# CarelessWISPer_alphaPCB.net
KiCad netlist of a schematic drawn in EAGLE
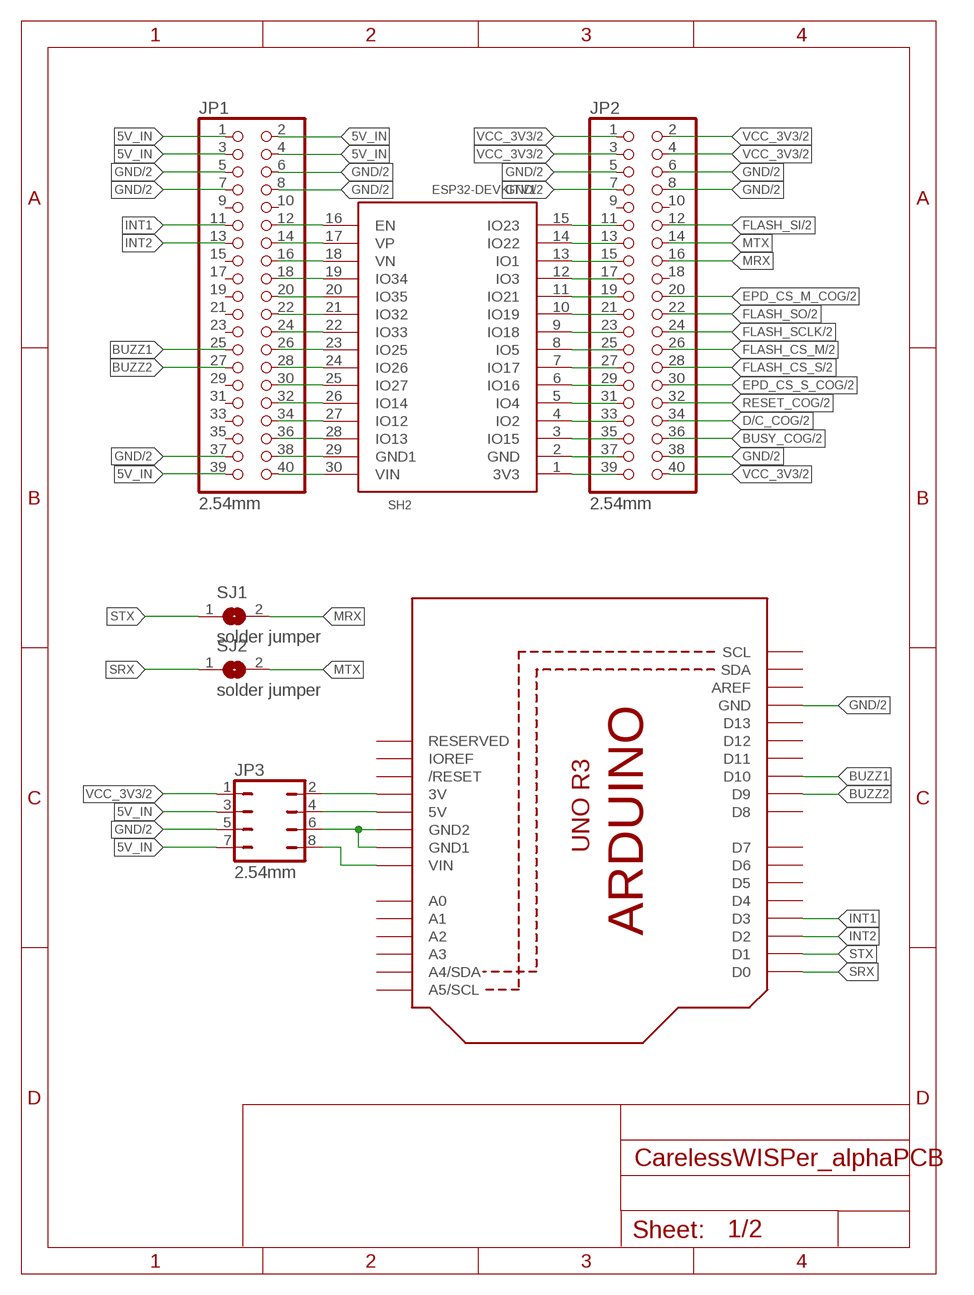
[diagram p0: schematic, sheet 1]
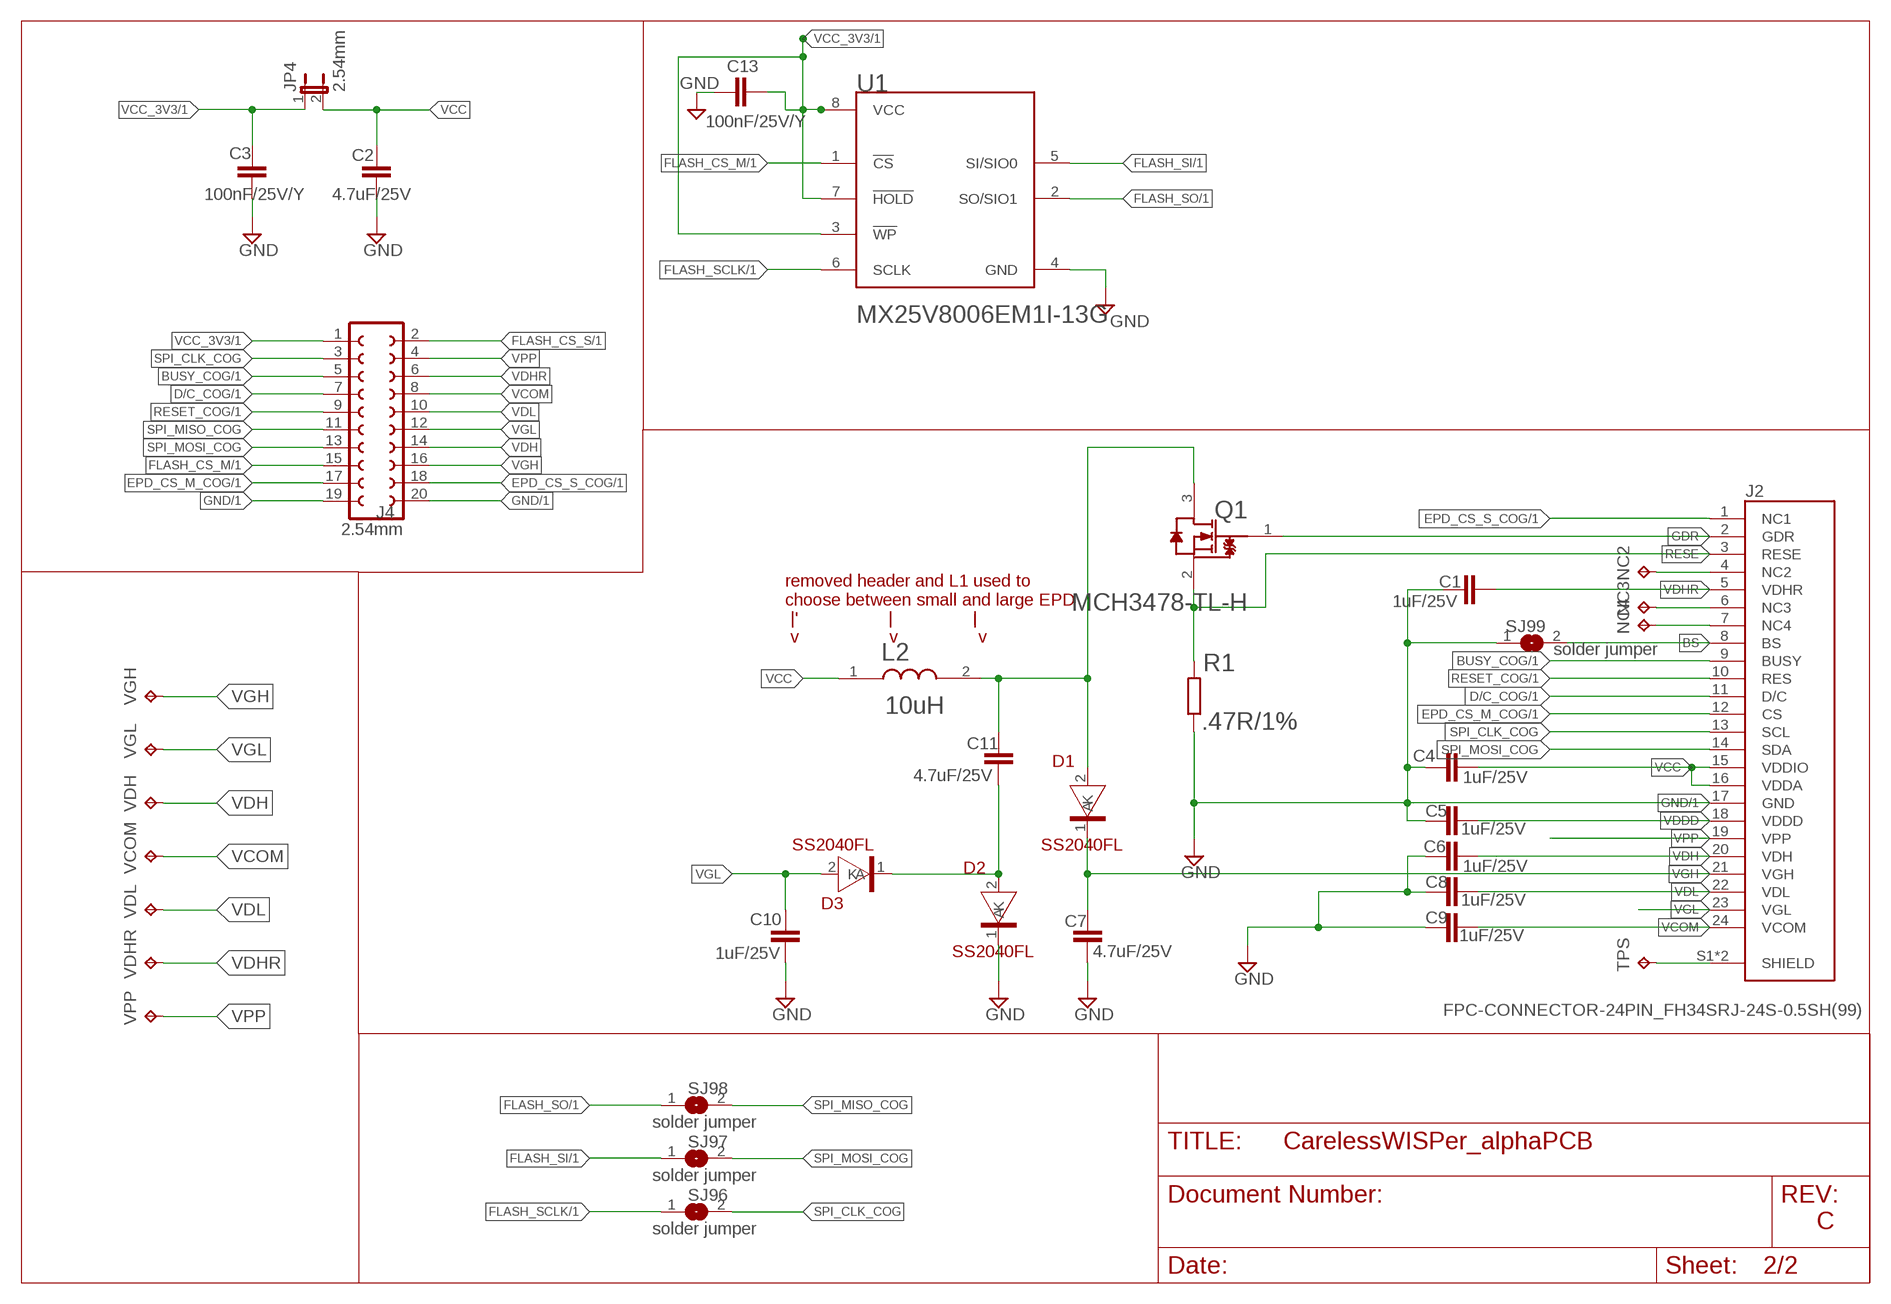
[diagram p1: schematic, sheet 2]

(export (version "E")
  (design (tool "Eeschema 10.0.6"))
  (components
    (comp (ref "JP1")
      (value "2.54mm")
      (footprint "eagle-import:2X20")
      (libsource (lib "eagle-import") (part "PINHD-2X20"))
    )
    (comp (ref "JP2")
      (value "2.54mm")
      (footprint "eagle-import:2X20")
      (libsource (lib "eagle-import") (part "PINHD-2X20"))
    )
    (comp (ref "JP3")
      (value "2.54mm")
      (footprint "eagle-import:JP4Q")
      (libsource (lib "eagle-import") (part "JP4Q"))
    )
    (comp (ref "SH1")
      (value "ARDUINOR3-BPLACE")
      (footprint "eagle-import:ARDUINOR3-BPLACE")
      (libsource (lib "eagle-import") (part "ARDUINOR3-BPLACE"))
    )
    (comp (ref "SH2")
      (value "ESP32-DEVKIT1_FIX")
      (footprint "eagle-import:ESP32-DEVKITV1")
      (libsource (lib "eagle-import") (part "ESP32-DEVKIT1_FIX"))
    )
    (comp (ref "SJ1")
      (value "solder jumper")
      (footprint "eagle-import:SJ")
      (libsource (lib "eagle-import") (part "SJ"))
    )
    (comp (ref "SJ2")
      (value "solder jumper")
      (footprint "eagle-import:SJ")
      (libsource (lib "eagle-import") (part "SJ"))
    )
    (comp (ref "C1")
      (value "1uF/25V")
      (footprint "eagle-import:CAPC2012X110")
      (libsource (lib "eagle-import") (part "CCHIP-0805(2012-METRIC)_"))
    )
    (comp (ref "C2")
      (value "4.7uF/25V")
      (footprint "eagle-import:CAPC2012X110")
      (libsource (lib "eagle-import") (part "CCHIP-0805(2012-METRIC)_"))
    )
    (comp (ref "C3")
      (value "100nF/25V/Y")
      (footprint "eagle-import:CAPC2012X110")
      (libsource (lib "eagle-import") (part "CCHIP-0805(2012-METRIC)_"))
    )
    (comp (ref "C4")
      (value "1uF/25V")
      (footprint "eagle-import:CAPC2012X110")
      (libsource (lib "eagle-import") (part "CCHIP-0805(2012-METRIC)_"))
    )
    (comp (ref "C5")
      (value "1uF/25V")
      (footprint "eagle-import:CAPC2012X110")
      (libsource (lib "eagle-import") (part "CCHIP-0805(2012-METRIC)_"))
    )
    (comp (ref "C6")
      (value "1uF/25V")
      (footprint "eagle-import:CAPC2012X110")
      (libsource (lib "eagle-import") (part "CCHIP-0805(2012-METRIC)_"))
    )
    (comp (ref "C7")
      (value "4.7uF/25V")
      (footprint "eagle-import:CAPC2012X110")
      (libsource (lib "eagle-import") (part "CCHIP-0805(2012-METRIC)_"))
    )
    (comp (ref "C8")
      (value "1uF/25V")
      (footprint "eagle-import:CAPC2012X110")
      (libsource (lib "eagle-import") (part "CCHIP-0805(2012-METRIC)_"))
    )
    (comp (ref "C9")
      (value "1uF/25V")
      (footprint "eagle-import:CAPC2012X110")
      (libsource (lib "eagle-import") (part "CCHIP-0805(2012-METRIC)_"))
    )
    (comp (ref "C10")
      (value "1uF/25V")
      (footprint "eagle-import:CAPC2012X110")
      (libsource (lib "eagle-import") (part "CCHIP-0805(2012-METRIC)_"))
    )
    (comp (ref "C11")
      (value "4.7uF/25V")
      (footprint "eagle-import:CAPC2012X110")
      (libsource (lib "eagle-import") (part "CCHIP-0805(2012-METRIC)_"))
    )
    (comp (ref "C13")
      (value "100nF/25V/Y")
      (footprint "eagle-import:CAPC2012X110")
      (libsource (lib "eagle-import") (part "CCHIP-0805(2012-METRIC)_"))
    )
    (comp (ref "D1")
      (value "SS2040FL")
      (footprint "eagle-import:SOD-123FL")
      (fields (field (name "MF") "Panjit"))
      (libsource (lib "eagle-import") (part "SS2040FL"))
    )
    (comp (ref "D2")
      (value "SS2040FL")
      (footprint "eagle-import:SOD-123FL")
      (fields (field (name "MF") "Panjit"))
      (libsource (lib "eagle-import") (part "SS2040FL"))
    )
    (comp (ref "D3")
      (value "SS2040FL")
      (footprint "eagle-import:SOD-123FL")
      (fields (field (name "MF") "Panjit"))
      (libsource (lib "eagle-import") (part "SS2040FL"))
    )
    (comp (ref "J2")
      (value "FPC-CONNECTOR-24PIN_FH34SRJ-24S-0.5SH(99)")
      (footprint "eagle-import:FPC-CONNECTOR-24PIN_HRS_FH34SRJ-24S-0.5SH(99)")
      (fields (field (name "MF") "Hirose Electric") (field (name "MP") "FH34SRJ-24S-0.5SH(99)"))
      (libsource (lib "eagle-import") (part "FPC-CONNECTOR-24PIN_FH34SRJ-24S-0.5SH(99)"))
    )
    (comp (ref "J4")
      (value "2.54mm")
      (footprint "eagle-import:FE10-2W")
      (libsource (lib "eagle-import") (part "FE10-2W"))
    )
    (comp (ref "JP4")
      (value "2.54mm")
      (footprint "eagle-import:JP1")
      (libsource (lib "eagle-import") (part "JP1E"))
    )
    (comp (ref "L2")
      (value "MURATA_LQH3NPZ100MMELMURATA_LQH3NPZ100MMEL_0_0")
      (footprint "eagle-import:MURATA_LQH3NPZ100MMEL_0")
      (fields
        (field (name "MF") "Murata")
        (field (name "MPN") "LQH3NPZ100MMEL")
        (field (name "TOLERANCE") "0.2")
      )
      (libsource (lib "eagle-import") (part "MURATA_LQH3NPZ100MMELMURATA_LQH3NPZ100MMEL_0_0"))
    )
    (comp (ref "NC2")
      (value "TPB1,27")
      (footprint "eagle-import:B1,27")
      (libsource (lib "eagle-import") (part "TPB1,27"))
    )
    (comp (ref "NC3")
      (value "TPB1,27")
      (footprint "eagle-import:B1,27")
      (libsource (lib "eagle-import") (part "TPB1,27"))
    )
    (comp (ref "NC4")
      (value "TPB1,27")
      (footprint "eagle-import:B1,27")
      (libsource (lib "eagle-import") (part "TPB1,27"))
    )
    (comp (ref "Q1")
      (value "ON_SEMICONDUCTOR_MCH3478-TL-HON_SEMICONDUCTOR_MCH3478-TL-H_0_0")
      (footprint "eagle-import:ON_SEMICONDUCTOR_MCH3478-TL-H_0")
      (fields (field (name "MF") "On Semiconductor") (field (name "MPN") "MCH3478-TL-H"))
      (libsource (lib "eagle-import") (part "ON_SEMICONDUCTOR_MCH3478-TL-HON_SEMICONDUCTOR_MCH3478-TL-H_0_0"))
    )
    (comp (ref "R1")
      (value ".47R/1%")
      (footprint "eagle-import:RESC2012X65")
      (libsource (lib "eagle-import") (part "RCHIP-0805(2012-METRIC)_"))
    )
    (comp (ref "SJ96")
      (value "solder jumper")
      (footprint "eagle-import:SJ")
      (libsource (lib "eagle-import") (part "SJ"))
    )
    (comp (ref "SJ97")
      (value "solder jumper")
      (footprint "eagle-import:SJ")
      (libsource (lib "eagle-import") (part "SJ"))
    )
    (comp (ref "SJ98")
      (value "solder jumper")
      (footprint "eagle-import:SJ")
      (libsource (lib "eagle-import") (part "SJ"))
    )
    (comp (ref "SJ99")
      (value "solder jumper")
      (footprint "eagle-import:SJ")
      (libsource (lib "eagle-import") (part "SJ"))
    )
    (comp (ref "TPS")
      (value "TPB1,27")
      (footprint "eagle-import:B1,27")
      (libsource (lib "eagle-import") (part "TPB1,27"))
    )
    (comp (ref "U1")
      (value "MACRONIX_MX25V8006EM1I-13GMACRONIX_MX25V8006EM1I-13G_0_0")
      (footprint "eagle-import:MACRONIX_MX25V8006EM1I-13G_0")
      (fields
        (field (name "3DS_PART_NUMBER") "521-00003")
        (field (name "DIGIKEY_PART_NUMBER") "1092-1118-ND")
        (field (name "MF") "Macronix")
      )
      (libsource (lib "eagle-import") (part "MACRONIX_MX25V8006EM1I-13GMACRONIX_MX25V8006EM1I-13G_0_0"))
    )
    (comp (ref "VCOM")
      (value "TPB1,27")
      (footprint "eagle-import:B1,27")
      (libsource (lib "eagle-import") (part "TPB1,27"))
    )
    (comp (ref "VDH")
      (value "TPB1,27")
      (footprint "eagle-import:B1,27")
      (libsource (lib "eagle-import") (part "TPB1,27"))
    )
    (comp (ref "VDHR")
      (value "TPB1,27")
      (footprint "eagle-import:B1,27")
      (libsource (lib "eagle-import") (part "TPB1,27"))
    )
    (comp (ref "VDL")
      (value "TPB1,27")
      (footprint "eagle-import:B1,27")
      (libsource (lib "eagle-import") (part "TPB1,27"))
    )
    (comp (ref "VGH")
      (value "TPB1,27")
      (footprint "eagle-import:B1,27")
      (libsource (lib "eagle-import") (part "TPB1,27"))
    )
    (comp (ref "VGL")
      (value "TPB1,27")
      (footprint "eagle-import:B1,27")
      (libsource (lib "eagle-import") (part "TPB1,27"))
    )
    (comp (ref "VPP")
      (value "TPB1,27")
      (footprint "eagle-import:B1,27")
      (libsource (lib "eagle-import") (part "TPB1,27"))
    )
  )
  (nets
    (net (code "1") (name "5V_IN") (class "Default")
      (node (ref "JP1") (pin "1") (pinfunction "1_1") (pintype "passive"))
      (node (ref "JP1") (pin "2") (pinfunction "2_2") (pintype "passive"))
      (node (ref "JP1") (pin "3") (pinfunction "3_3") (pintype "passive"))
      (node (ref "JP1") (pin "39") (pinfunction "39_39") (pintype "passive"))
      (node (ref "JP1") (pin "4") (pinfunction "4_4") (pintype "passive"))
      (node (ref "JP3") (pin "3") (pinfunction "3_3") (pintype "passive"))
      (node (ref "JP3") (pin "7") (pinfunction "7_7") (pintype "passive"))
    )
    (net (code "2") (name "BS") (class "Default")
      (node (ref "J2") (pin "8") (pinfunction "BS_8") (pintype "passive"))
      (node (ref "SJ99") (pin "2") (pinfunction "2_2") (pintype "passive"))
    )
    (net (code "3") (name "BUSY_COG") (class "Default")
      (node (ref "J2") (pin "9") (pinfunction "BUSY_9") (pintype "passive"))
      (node (ref "J4") (pin "5") (pinfunction "5_5") (pintype "passive"))
      (node (ref "JP2") (pin "36") (pinfunction "36_36") (pintype "passive"))
    )
    (net (code "4") (name "BUZZ1") (class "Default")
      (node (ref "JP1") (pin "25") (pinfunction "25_25") (pintype "passive"))
      (node (ref "SH1") (pin "D10") (pinfunction "D10_D10") (pintype "bidirectional"))
    )
    (net (code "5") (name "BUZZ2") (class "Default")
      (node (ref "JP1") (pin "27") (pinfunction "27_27") (pintype "passive"))
      (node (ref "SH1") (pin "D9") (pinfunction "D9_D9") (pintype "bidirectional"))
    )
    (net (code "6") (name "D{slash}C_COG") (class "Default")
      (node (ref "J2") (pin "11") (pinfunction "D/C_11") (pintype "passive"))
      (node (ref "J4") (pin "7") (pinfunction "7_7") (pintype "passive"))
      (node (ref "JP2") (pin "34") (pinfunction "34_34") (pintype "passive"))
    )
    (net (code "7") (name "EPD_CS_M_COG") (class "Default")
      (node (ref "J2") (pin "12") (pinfunction "CS_12") (pintype "passive"))
      (node (ref "J4") (pin "17") (pinfunction "17_17") (pintype "passive"))
      (node (ref "JP2") (pin "20") (pinfunction "20_20") (pintype "passive"))
    )
    (net (code "8") (name "EPD_CS_S_COG") (class "Default")
      (node (ref "J2") (pin "1") (pinfunction "NC1_1") (pintype "passive"))
      (node (ref "J4") (pin "18") (pinfunction "18_18") (pintype "passive"))
      (node (ref "JP2") (pin "30") (pinfunction "30_30") (pintype "passive"))
    )
    (net (code "9") (name "FLASH_CS_M") (class "Default")
      (node (ref "J4") (pin "15") (pinfunction "15_15") (pintype "passive"))
      (node (ref "JP2") (pin "26") (pinfunction "26_26") (pintype "passive"))
      (node (ref "U1") (pin "1") (pinfunction "~{CS}_1") (pintype "input"))
    )
    (net (code "10") (name "FLASH_CS_S") (class "Default")
      (node (ref "J4") (pin "2") (pinfunction "2_2") (pintype "passive"))
      (node (ref "JP2") (pin "28") (pinfunction "28_28") (pintype "passive"))
    )
    (net (code "11") (name "FLASH_SCLK") (class "Default")
      (node (ref "JP2") (pin "24") (pinfunction "24_24") (pintype "passive"))
      (node (ref "SJ96") (pin "1") (pinfunction "1_1") (pintype "passive"))
      (node (ref "U1") (pin "6") (pinfunction "SCLK_6") (pintype "input"))
    )
    (net (code "12") (name "FLASH_SI") (class "Default")
      (node (ref "JP2") (pin "12") (pinfunction "12_12") (pintype "passive"))
      (node (ref "SJ97") (pin "1") (pinfunction "1_1") (pintype "passive"))
      (node (ref "U1") (pin "5") (pinfunction "SI/SIO0_5") (pintype "bidirectional"))
    )
    (net (code "13") (name "FLASH_SO") (class "Default")
      (node (ref "JP2") (pin "22") (pinfunction "22_22") (pintype "passive"))
      (node (ref "SJ98") (pin "1") (pinfunction "1_1") (pintype "passive"))
      (node (ref "U1") (pin "2") (pinfunction "SO/SIO1_2") (pintype "bidirectional"))
    )
    (net (code "14") (name "GDR") (class "Default")
      (node (ref "J2") (pin "2") (pinfunction "GDR_2") (pintype "passive"))
      (node (ref "Q1") (pin "1") (pinfunction "G_1") (pintype "passive"))
    )
    (net (code "15") (name "GND") (class "Default")
      (node (ref "C1") (pin "1") (pinfunction "1_1") (pintype "passive"))
      (node (ref "C10") (pin "2") (pinfunction "2_2") (pintype "passive"))
      (node (ref "C13") (pin "1") (pinfunction "1_1") (pintype "passive"))
      (node (ref "C2") (pin "1") (pinfunction "1_1") (pintype "passive"))
      (node (ref "C3") (pin "1") (pinfunction "1_1") (pintype "passive"))
      (node (ref "C4") (pin "2") (pinfunction "2_2") (pintype "passive"))
      (node (ref "C5") (pin "2") (pinfunction "2_2") (pintype "passive"))
      (node (ref "C6") (pin "2") (pinfunction "2_2") (pintype "passive"))
      (node (ref "C7") (pin "1") (pinfunction "1_1") (pintype "passive"))
      (node (ref "C8") (pin "2") (pinfunction "2_2") (pintype "passive"))
      (node (ref "C9") (pin "2") (pinfunction "2_2") (pintype "passive"))
      (node (ref "D2") (pin "1") (pinfunction "K_1") (pintype "passive"))
      (node (ref "J2") (pin "17") (pinfunction "GND_17") (pintype "passive"))
      (node (ref "J4") (pin "19") (pinfunction "19_19") (pintype "passive"))
      (node (ref "J4") (pin "20") (pinfunction "20_20") (pintype "passive"))
      (node (ref "JP1") (pin "37") (pinfunction "37_37") (pintype "passive"))
      (node (ref "JP1") (pin "5") (pinfunction "5_5") (pintype "passive"))
      (node (ref "JP1") (pin "6") (pinfunction "6_6") (pintype "passive"))
      (node (ref "JP1") (pin "7") (pinfunction "7_7") (pintype "passive"))
      (node (ref "JP1") (pin "8") (pinfunction "8_8") (pintype "passive"))
      (node (ref "JP2") (pin "38") (pinfunction "38_38") (pintype "passive"))
      (node (ref "JP2") (pin "5") (pinfunction "5_5") (pintype "passive"))
      (node (ref "JP2") (pin "6") (pinfunction "6_6") (pintype "passive"))
      (node (ref "JP2") (pin "7") (pinfunction "7_7") (pintype "passive"))
      (node (ref "JP2") (pin "8") (pinfunction "8_8") (pintype "passive"))
      (node (ref "JP3") (pin "5") (pinfunction "5_5") (pintype "passive"))
      (node (ref "R1") (pin "1") (pinfunction "1_1") (pintype "passive"))
      (node (ref "SH1") (pin "GND") (pinfunction "GND_GND") (pintype "power_in"))
      (node (ref "SJ99") (pin "1") (pinfunction "1_1") (pintype "passive"))
      (node (ref "U1") (pin "4") (pinfunction "GND_4") (pintype "power_in"))
    )
    (net (code "16") (name "INT1") (class "Default")
      (node (ref "JP1") (pin "11") (pinfunction "11_11") (pintype "passive"))
      (node (ref "SH1") (pin "D3") (pinfunction "D3_D3") (pintype "bidirectional"))
    )
    (net (code "17") (name "INT2") (class "Default")
      (node (ref "JP1") (pin "13") (pinfunction "13_13") (pintype "passive"))
      (node (ref "SH1") (pin "D2") (pinfunction "D2_D2") (pintype "bidirectional"))
    )
    (net (code "18") (name "MRX") (class "Default")
      (node (ref "JP2") (pin "16") (pinfunction "16_16") (pintype "passive"))
      (node (ref "SJ1") (pin "2") (pinfunction "2_2") (pintype "passive"))
    )
    (net (code "19") (name "MTX") (class "Default")
      (node (ref "JP2") (pin "14") (pinfunction "14_14") (pintype "passive"))
      (node (ref "SJ2") (pin "2") (pinfunction "2_2") (pintype "passive"))
    )
    (net (code "20") (name "Net-(D1-A)") (class "Default")
      (node (ref "C11") (pin "2") (pinfunction "2_2") (pintype "passive"))
      (node (ref "D1") (pin "2") (pinfunction "A_2") (pintype "passive"))
      (node (ref "L2") (pin "2") (pinfunction "2_2") (pintype "passive"))
      (node (ref "Q1") (pin "3") (pinfunction "D_3") (pintype "passive"))
    )
    (net (code "21") (name "Net-(D2-A)") (class "Default")
      (node (ref "C11") (pin "1") (pinfunction "1_1") (pintype "passive"))
      (node (ref "D2") (pin "2") (pinfunction "A_2") (pintype "passive"))
      (node (ref "D3") (pin "1") (pinfunction "K_1") (pintype "passive"))
    )
    (net (code "22") (name "Net-(J2-NC2)") (class "Default")
      (node (ref "J2") (pin "4") (pinfunction "NC2_4") (pintype "passive"))
      (node (ref "NC2") (pin "TP") (pinfunction "TP_TP") (pintype "input"))
    )
    (net (code "23") (name "Net-(J2-NC3)") (class "Default")
      (node (ref "J2") (pin "6") (pinfunction "NC3_6") (pintype "passive"))
      (node (ref "NC3") (pin "TP") (pinfunction "TP_TP") (pintype "input"))
    )
    (net (code "24") (name "Net-(J2-NC4)") (class "Default")
      (node (ref "J2") (pin "7") (pinfunction "NC4_7") (pintype "passive"))
      (node (ref "NC4") (pin "TP") (pinfunction "TP_TP") (pintype "input"))
    )
    (net (code "25") (name "Net-(J2-SHIELD-PadS1)") (class "Default")
      (node (ref "J2") (pin "S1") (pinfunction "SHIELD_S1") (pintype "passive"))
      (node (ref "J2") (pin "S2") (pinfunction "SHIELD_S2") (pintype "passive"))
      (node (ref "TPS") (pin "TP") (pinfunction "TP_TP") (pintype "input"))
    )
    (net (code "26") (name "Net-(JP3-Pad2)") (class "Default")
      (node (ref "JP3") (pin "2") (pinfunction "2_2") (pintype "passive"))
      (node (ref "SH1") (pin "3V") (pinfunction "3V_3V") (pintype "power_in"))
    )
    (net (code "27") (name "Net-(JP3-Pad4)") (class "Default")
      (node (ref "JP3") (pin "4") (pinfunction "4_4") (pintype "passive"))
      (node (ref "SH1") (pin "5V") (pinfunction "5V_5V") (pintype "power_in"))
    )
    (net (code "28") (name "Net-(JP3-Pad6)") (class "Default")
      (node (ref "JP3") (pin "6") (pinfunction "6_6") (pintype "passive"))
      (node (ref "SH1") (pin "GND1") (pinfunction "GND1_GND1") (pintype "power_in"))
      (node (ref "SH1") (pin "GND2") (pinfunction "GND2_GND2") (pintype "power_in"))
    )
    (net (code "29") (name "Net-(JP3-Pad8)") (class "Default")
      (node (ref "JP3") (pin "8") (pinfunction "8_8") (pintype "passive"))
      (node (ref "SH1") (pin "VIN") (pinfunction "VIN_VIN") (pintype "power_in"))
    )
    (net (code "30") (name "Net-(SH2-3V3)") (class "Default")
      (node (ref "JP2") (pin "39") (pinfunction "39_39") (pintype "passive"))
      (node (ref "SH2") (pin "1") (pinfunction "3V3_1") (pintype "bidirectional"))
    )
    (net (code "31") (name "Net-(SH2-EN)") (class "Default")
      (node (ref "JP1") (pin "12") (pinfunction "12_12") (pintype "passive"))
      (node (ref "SH2") (pin "16") (pinfunction "EN_16") (pintype "bidirectional"))
    )
    (net (code "32") (name "Net-(SH2-GND)") (class "Default")
      (node (ref "JP2") (pin "37") (pinfunction "37_37") (pintype "passive"))
      (node (ref "SH2") (pin "2") (pinfunction "GND_2") (pintype "bidirectional"))
    )
    (net (code "33") (name "Net-(SH2-GND1)") (class "Default")
      (node (ref "JP1") (pin "38") (pinfunction "38_38") (pintype "passive"))
      (node (ref "SH2") (pin "29") (pinfunction "GND1_29") (pintype "bidirectional"))
    )
    (net (code "34") (name "Net-(SH2-IO1)") (class "Default")
      (node (ref "JP2") (pin "15") (pinfunction "15_15") (pintype "passive"))
      (node (ref "SH2") (pin "13") (pinfunction "IO1_13") (pintype "bidirectional"))
    )
    (net (code "35") (name "Net-(SH2-IO2)") (class "Default")
      (node (ref "JP2") (pin "33") (pinfunction "33_33") (pintype "passive"))
      (node (ref "SH2") (pin "4") (pinfunction "IO2_4") (pintype "bidirectional"))
    )
    (net (code "36") (name "Net-(SH2-IO3)") (class "Default")
      (node (ref "JP2") (pin "17") (pinfunction "17_17") (pintype "passive"))
      (node (ref "SH2") (pin "12") (pinfunction "IO3_12") (pintype "bidirectional"))
    )
    (net (code "37") (name "Net-(SH2-IO4)") (class "Default")
      (node (ref "JP2") (pin "31") (pinfunction "31_31") (pintype "passive"))
      (node (ref "SH2") (pin "5") (pinfunction "IO4_5") (pintype "bidirectional"))
    )
    (net (code "38") (name "Net-(SH2-IO5)") (class "Default")
      (node (ref "JP2") (pin "25") (pinfunction "25_25") (pintype "passive"))
      (node (ref "SH2") (pin "8") (pinfunction "IO5_8") (pintype "bidirectional"))
    )
    (net (code "39") (name "Net-(SH2-IO12)") (class "Default")
      (node (ref "JP1") (pin "34") (pinfunction "34_34") (pintype "passive"))
      (node (ref "SH2") (pin "27") (pinfunction "IO12_27") (pintype "bidirectional"))
    )
    (net (code "40") (name "Net-(SH2-IO13)") (class "Default")
      (node (ref "JP1") (pin "36") (pinfunction "36_36") (pintype "passive"))
      (node (ref "SH2") (pin "28") (pinfunction "IO13_28") (pintype "bidirectional"))
    )
    (net (code "41") (name "Net-(SH2-IO14)") (class "Default")
      (node (ref "JP1") (pin "32") (pinfunction "32_32") (pintype "passive"))
      (node (ref "SH2") (pin "26") (pinfunction "IO14_26") (pintype "bidirectional"))
    )
    (net (code "42") (name "Net-(SH2-IO15)") (class "Default")
      (node (ref "JP2") (pin "35") (pinfunction "35_35") (pintype "passive"))
      (node (ref "SH2") (pin "3") (pinfunction "IO15_3") (pintype "bidirectional"))
    )
    (net (code "43") (name "Net-(SH2-IO16)") (class "Default")
      (node (ref "JP2") (pin "29") (pinfunction "29_29") (pintype "passive"))
      (node (ref "SH2") (pin "6") (pinfunction "IO16_6") (pintype "bidirectional"))
    )
    (net (code "44") (name "Net-(SH2-IO17)") (class "Default")
      (node (ref "JP2") (pin "27") (pinfunction "27_27") (pintype "passive"))
      (node (ref "SH2") (pin "7") (pinfunction "IO17_7") (pintype "bidirectional"))
    )
    (net (code "45") (name "Net-(SH2-IO18)") (class "Default")
      (node (ref "JP2") (pin "23") (pinfunction "23_23") (pintype "passive"))
      (node (ref "SH2") (pin "9") (pinfunction "IO18_9") (pintype "bidirectional"))
    )
    (net (code "46") (name "Net-(SH2-IO19)") (class "Default")
      (node (ref "JP2") (pin "21") (pinfunction "21_21") (pintype "passive"))
      (node (ref "SH2") (pin "10") (pinfunction "IO19_10") (pintype "bidirectional"))
    )
    (net (code "47") (name "Net-(SH2-IO21)") (class "Default")
      (node (ref "JP2") (pin "19") (pinfunction "19_19") (pintype "passive"))
      (node (ref "SH2") (pin "11") (pinfunction "IO21_11") (pintype "bidirectional"))
    )
    (net (code "48") (name "Net-(SH2-IO22)") (class "Default")
      (node (ref "JP2") (pin "13") (pinfunction "13_13") (pintype "passive"))
      (node (ref "SH2") (pin "14") (pinfunction "IO22_14") (pintype "bidirectional"))
    )
    (net (code "49") (name "Net-(SH2-IO23)") (class "Default")
      (node (ref "JP2") (pin "11") (pinfunction "11_11") (pintype "passive"))
      (node (ref "SH2") (pin "15") (pinfunction "IO23_15") (pintype "bidirectional"))
    )
    (net (code "50") (name "Net-(SH2-IO25)") (class "Default")
      (node (ref "JP1") (pin "26") (pinfunction "26_26") (pintype "passive"))
      (node (ref "SH2") (pin "23") (pinfunction "IO25_23") (pintype "bidirectional"))
    )
    (net (code "51") (name "Net-(SH2-IO26)") (class "Default")
      (node (ref "JP1") (pin "28") (pinfunction "28_28") (pintype "passive"))
      (node (ref "SH2") (pin "24") (pinfunction "IO26_24") (pintype "bidirectional"))
    )
    (net (code "52") (name "Net-(SH2-IO27)") (class "Default")
      (node (ref "JP1") (pin "30") (pinfunction "30_30") (pintype "passive"))
      (node (ref "SH2") (pin "25") (pinfunction "IO27_25") (pintype "bidirectional"))
    )
    (net (code "53") (name "Net-(SH2-IO32)") (class "Default")
      (node (ref "JP1") (pin "22") (pinfunction "22_22") (pintype "passive"))
      (node (ref "SH2") (pin "21") (pinfunction "IO32_21") (pintype "bidirectional"))
    )
    (net (code "54") (name "Net-(SH2-IO33)") (class "Default")
      (node (ref "JP1") (pin "24") (pinfunction "24_24") (pintype "passive"))
      (node (ref "SH2") (pin "22") (pinfunction "IO33_22") (pintype "bidirectional"))
    )
    (net (code "55") (name "Net-(SH2-IO34)") (class "Default")
      (node (ref "JP1") (pin "18") (pinfunction "18_18") (pintype "passive"))
      (node (ref "SH2") (pin "19") (pinfunction "IO34_19") (pintype "bidirectional"))
    )
    (net (code "56") (name "Net-(SH2-IO35)") (class "Default")
      (node (ref "JP1") (pin "20") (pinfunction "20_20") (pintype "passive"))
      (node (ref "SH2") (pin "20") (pinfunction "IO35_20") (pintype "bidirectional"))
    )
    (net (code "57") (name "Net-(SH2-VIN)") (class "Default")
      (node (ref "JP1") (pin "40") (pinfunction "40_40") (pintype "passive"))
      (node (ref "SH2") (pin "30") (pinfunction "VIN_30") (pintype "bidirectional"))
    )
    (net (code "58") (name "Net-(SH2-VN)") (class "Default")
      (node (ref "JP1") (pin "16") (pinfunction "16_16") (pintype "passive"))
      (node (ref "SH2") (pin "18") (pinfunction "VN_18") (pintype "bidirectional"))
    )
    (net (code "59") (name "Net-(SH2-VP)") (class "Default")
      (node (ref "JP1") (pin "14") (pinfunction "14_14") (pintype "passive"))
      (node (ref "SH2") (pin "17") (pinfunction "VP_17") (pintype "bidirectional"))
    )
    (net (code "60") (name "RESE") (class "Default")
      (node (ref "J2") (pin "3") (pinfunction "RESE_3") (pintype "passive"))
      (node (ref "Q1") (pin "2") (pinfunction "S_2") (pintype "passive"))
      (node (ref "R1") (pin "2") (pinfunction "2_2") (pintype "passive"))
    )
    (net (code "61") (name "RESET_COG") (class "Default")
      (node (ref "J2") (pin "10") (pinfunction "RES_10") (pintype "passive"))
      (node (ref "J4") (pin "9") (pinfunction "9_9") (pintype "passive"))
      (node (ref "JP2") (pin "32") (pinfunction "32_32") (pintype "passive"))
    )
    (net (code "62") (name "SPI_CLK_COG") (class "Default")
      (node (ref "J2") (pin "13") (pinfunction "SCL_13") (pintype "passive"))
      (node (ref "J4") (pin "3") (pinfunction "3_3") (pintype "passive"))
      (node (ref "SJ96") (pin "2") (pinfunction "2_2") (pintype "passive"))
    )
    (net (code "63") (name "SPI_MISO_COG") (class "Default")
      (node (ref "J4") (pin "11") (pinfunction "11_11") (pintype "passive"))
      (node (ref "SJ98") (pin "2") (pinfunction "2_2") (pintype "passive"))
    )
    (net (code "64") (name "SPI_MOSI_COG") (class "Default")
      (node (ref "J2") (pin "14") (pinfunction "SDA_14") (pintype "passive"))
      (node (ref "J4") (pin "13") (pinfunction "13_13") (pintype "passive"))
      (node (ref "SJ97") (pin "2") (pinfunction "2_2") (pintype "passive"))
    )
    (net (code "65") (name "SRX") (class "Default")
      (node (ref "SH1") (pin "D0") (pinfunction "D0_D0") (pintype "bidirectional"))
      (node (ref "SJ2") (pin "1") (pinfunction "1_1") (pintype "passive"))
    )
    (net (code "66") (name "STX") (class "Default")
      (node (ref "SH1") (pin "D1") (pinfunction "D1_D1") (pintype "bidirectional"))
      (node (ref "SJ1") (pin "1") (pinfunction "1_1") (pintype "passive"))
    )
    (net (code "67") (name "VCC") (class "Default")
      (node (ref "C2") (pin "2") (pinfunction "2_2") (pintype "passive"))
      (node (ref "C4") (pin "1") (pinfunction "1_1") (pintype "passive"))
      (node (ref "J2") (pin "15") (pinfunction "VDDIO_15") (pintype "passive"))
      (node (ref "J2") (pin "16") (pinfunction "VDDA_16") (pintype "passive"))
      (node (ref "JP4") (pin "2") (pinfunction "2_2") (pintype "passive"))
      (node (ref "L2") (pin "1") (pinfunction "1_1") (pintype "passive"))
    )
    (net (code "68") (name "VCC_3V3") (class "Default")
      (node (ref "C13") (pin "2") (pinfunction "2_2") (pintype "passive"))
      (node (ref "C3") (pin "2") (pinfunction "2_2") (pintype "passive"))
      (node (ref "J4") (pin "1") (pinfunction "1_1") (pintype "passive"))
      (node (ref "JP2") (pin "1") (pinfunction "1_1") (pintype "passive"))
      (node (ref "JP2") (pin "2") (pinfunction "2_2") (pintype "passive"))
      (node (ref "JP2") (pin "3") (pinfunction "3_3") (pintype "passive"))
      (node (ref "JP2") (pin "4") (pinfunction "4_4") (pintype "passive"))
      (node (ref "JP2") (pin "40") (pinfunction "40_40") (pintype "passive"))
      (node (ref "JP3") (pin "1") (pinfunction "1_1") (pintype "passive"))
      (node (ref "JP4") (pin "1") (pinfunction "1_1") (pintype "passive"))
      (node (ref "U1") (pin "3") (pinfunction "~{WP}_3") (pintype "input"))
      (node (ref "U1") (pin "7") (pinfunction "~{HOLD}_7") (pintype "input"))
      (node (ref "U1") (pin "8") (pinfunction "VCC_8") (pintype "power_in"))
    )
    (net (code "69") (name "VCOM") (class "Default")
      (node (ref "C9") (pin "1") (pinfunction "1_1") (pintype "passive"))
      (node (ref "J2") (pin "24") (pinfunction "VCOM_24") (pintype "passive"))
      (node (ref "J4") (pin "8") (pinfunction "8_8") (pintype "passive"))
      (node (ref "VCOM") (pin "TP") (pinfunction "TP_TP") (pintype "input"))
    )
    (net (code "70") (name "VDDD") (class "Default")
      (node (ref "C5") (pin "1") (pinfunction "1_1") (pintype "passive"))
      (node (ref "J2") (pin "18") (pinfunction "VDDD_18") (pintype "passive"))
    )
    (net (code "71") (name "VDH") (class "Default")
      (node (ref "C6") (pin "1") (pinfunction "1_1") (pintype "passive"))
      (node (ref "J2") (pin "20") (pinfunction "VDH_20") (pintype "passive"))
      (node (ref "J4") (pin "14") (pinfunction "14_14") (pintype "passive"))
      (node (ref "VDH") (pin "TP") (pinfunction "TP_TP") (pintype "input"))
    )
    (net (code "72") (name "VDHR") (class "Default")
      (node (ref "C1") (pin "2") (pinfunction "2_2") (pintype "passive"))
      (node (ref "J2") (pin "5") (pinfunction "VDHR_5") (pintype "passive"))
      (node (ref "J4") (pin "6") (pinfunction "6_6") (pintype "passive"))
      (node (ref "VDHR") (pin "TP") (pinfunction "TP_TP") (pintype "input"))
    )
    (net (code "73") (name "VDL") (class "Default")
      (node (ref "C8") (pin "1") (pinfunction "1_1") (pintype "passive"))
      (node (ref "J2") (pin "22") (pinfunction "VDL_22") (pintype "passive"))
      (node (ref "J4") (pin "10") (pinfunction "10_10") (pintype "passive"))
      (node (ref "VDL") (pin "TP") (pinfunction "TP_TP") (pintype "input"))
    )
    (net (code "74") (name "VGH") (class "Default")
      (node (ref "C7") (pin "2") (pinfunction "2_2") (pintype "passive"))
      (node (ref "D1") (pin "1") (pinfunction "K_1") (pintype "passive"))
      (node (ref "J2") (pin "21") (pinfunction "VGH_21") (pintype "passive"))
      (node (ref "J4") (pin "16") (pinfunction "16_16") (pintype "passive"))
      (node (ref "VGH") (pin "TP") (pinfunction "TP_TP") (pintype "input"))
    )
    (net (code "75") (name "VGL") (class "Default")
      (node (ref "C10") (pin "1") (pinfunction "1_1") (pintype "passive"))
      (node (ref "D3") (pin "2") (pinfunction "A_2") (pintype "passive"))
      (node (ref "J2") (pin "23") (pinfunction "VGL_23") (pintype "passive"))
      (node (ref "J4") (pin "12") (pinfunction "12_12") (pintype "passive"))
      (node (ref "VGL") (pin "TP") (pinfunction "TP_TP") (pintype "input"))
    )
    (net (code "76") (name "VPP") (class "Default")
      (node (ref "J2") (pin "19") (pinfunction "VPP_19") (pintype "passive"))
      (node (ref "J4") (pin "4") (pinfunction "4_4") (pintype "passive"))
      (node (ref "VPP") (pin "TP") (pinfunction "TP_TP") (pintype "input"))
    )
    (net (code "77") (name "unconnected-(JP1-Pad9)") (class "Default")
      (node (ref "JP1") (pin "9") (pinfunction "9_9") (pintype "passive"))
    )
    (net (code "78") (name "unconnected-(JP1-Pad10)") (class "Default")
      (node (ref "JP1") (pin "10") (pinfunction "10_10") (pintype "passive"))
    )
    (net (code "79") (name "unconnected-(JP1-Pad15)") (class "Default")
      (node (ref "JP1") (pin "15") (pinfunction "15_15") (pintype "passive"))
    )
    (net (code "80") (name "unconnected-(JP1-Pad17)") (class "Default")
      (node (ref "JP1") (pin "17") (pinfunction "17_17") (pintype "passive"))
    )
    (net (code "81") (name "unconnected-(JP1-Pad19)") (class "Default")
      (node (ref "JP1") (pin "19") (pinfunction "19_19") (pintype "passive"))
    )
    (net (code "82") (name "unconnected-(JP1-Pad21)") (class "Default")
      (node (ref "JP1") (pin "21") (pinfunction "21_21") (pintype "passive"))
    )
    (net (code "83") (name "unconnected-(JP1-Pad23)") (class "Default")
      (node (ref "JP1") (pin "23") (pinfunction "23_23") (pintype "passive"))
    )
    (net (code "84") (name "unconnected-(JP1-Pad29)") (class "Default")
      (node (ref "JP1") (pin "29") (pinfunction "29_29") (pintype "passive"))
    )
    (net (code "85") (name "unconnected-(JP1-Pad31)") (class "Default")
      (node (ref "JP1") (pin "31") (pinfunction "31_31") (pintype "passive"))
    )
    (net (code "86") (name "unconnected-(JP1-Pad33)") (class "Default")
      (node (ref "JP1") (pin "33") (pinfunction "33_33") (pintype "passive"))
    )
    (net (code "87") (name "unconnected-(JP1-Pad35)") (class "Default")
      (node (ref "JP1") (pin "35") (pinfunction "35_35") (pintype "passive"))
    )
    (net (code "88") (name "unconnected-(JP2-Pad9)") (class "Default")
      (node (ref "JP2") (pin "9") (pinfunction "9_9") (pintype "passive"))
    )
    (net (code "89") (name "unconnected-(JP2-Pad10)") (class "Default")
      (node (ref "JP2") (pin "10") (pinfunction "10_10") (pintype "passive"))
    )
    (net (code "90") (name "unconnected-(JP2-Pad18)") (class "Default")
      (node (ref "JP2") (pin "18") (pinfunction "18_18") (pintype "passive"))
    )
    (net (code "91") (name "unconnected-(SH1-A4{slash}SDA-PadA4)") (class "Default")
      (node (ref "SH1") (pin "A4") (pinfunction "A4/SDA_A4") (pintype "bidirectional"))
    )
    (net (code "92") (name "unconnected-(SH1-A5{slash}SCL-PadA5)") (class "Default")
      (node (ref "SH1") (pin "A5") (pinfunction "A5/SCL_A5") (pintype "bidirectional"))
    )
    (net (code "93") (name "unconnected-(SH1-PadA0)") (class "Default")
      (node (ref "SH1") (pin "A0") (pinfunction "A0_A0") (pintype "bidirectional"))
    )
    (net (code "94") (name "unconnected-(SH1-PadA1)") (class "Default")
      (node (ref "SH1") (pin "A1") (pinfunction "A1_A1") (pintype "bidirectional"))
    )
    (net (code "95") (name "unconnected-(SH1-PadA2)") (class "Default")
      (node (ref "SH1") (pin "A2") (pinfunction "A2_A2") (pintype "bidirectional"))
    )
    (net (code "96") (name "unconnected-(SH1-PadA3)") (class "Default")
      (node (ref "SH1") (pin "A3") (pinfunction "A3_A3") (pintype "bidirectional"))
    )
    (net (code "97") (name "unconnected-(SH1-PadAREF)") (class "Default")
      (node (ref "SH1") (pin "AREF") (pinfunction "AREF_AREF") (pintype "bidirectional"))
    )
    (net (code "98") (name "unconnected-(SH1-PadD4)") (class "Default")
      (node (ref "SH1") (pin "D4") (pinfunction "D4_D4") (pintype "bidirectional"))
    )
    (net (code "99") (name "unconnected-(SH1-PadD5)") (class "Default")
      (node (ref "SH1") (pin "D5") (pinfunction "D5_D5") (pintype "bidirectional"))
    )
    (net (code "100") (name "unconnected-(SH1-PadD6)") (class "Default")
      (node (ref "SH1") (pin "D6") (pinfunction "D6_D6") (pintype "bidirectional"))
    )
    (net (code "101") (name "unconnected-(SH1-PadD7)") (class "Default")
      (node (ref "SH1") (pin "D7") (pinfunction "D7_D7") (pintype "bidirectional"))
    )
    (net (code "102") (name "unconnected-(SH1-PadD8)") (class "Default")
      (node (ref "SH1") (pin "D8") (pinfunction "D8_D8") (pintype "bidirectional"))
    )
    (net (code "103") (name "unconnected-(SH1-PadD11)") (class "Default")
      (node (ref "SH1") (pin "D11") (pinfunction "D11_D11") (pintype "bidirectional"))
    )
    (net (code "104") (name "unconnected-(SH1-PadD12)") (class "Default")
      (node (ref "SH1") (pin "D12") (pinfunction "D12_D12") (pintype "bidirectional"))
    )
    (net (code "105") (name "unconnected-(SH1-PadD13)") (class "Default")
      (node (ref "SH1") (pin "D13") (pinfunction "D13_D13") (pintype "bidirectional"))
    )
    (net (code "106") (name "unconnected-(SH1-PadIOREF)") (class "Default")
      (node (ref "SH1") (pin "IOREF") (pinfunction "IOREF_IOREF") (pintype "output"))
    )
    (net (code "107") (name "unconnected-(SH1-PadRESERVED)") (class "Default")
      (node (ref "SH1") (pin "RESERVED") (pinfunction "RESERVED_RESERVED") (pintype "no_connect"))
    )
    (net (code "108") (name "unconnected-(SH1-PadSCL)") (class "Default")
      (node (ref "SH1") (pin "SCL") (pinfunction "SCL_SCL") (pintype "bidirectional"))
    )
    (net (code "109") (name "unconnected-(SH1-PadSDA)") (class "Default")
      (node (ref "SH1") (pin "SDA") (pinfunction "SDA_SDA") (pintype "bidirectional"))
    )
    (net (code "110") (name "unconnected-(SH1-{slash}RESET-PadRESET)") (class "Default")
      (node (ref "SH1") (pin "RESET") (pinfunction "/RESET_RESET") (pintype "bidirectional"))
    )
  )
)
